# MCU_SCHEM_REV1.net
KiCad netlist of a schematic drawn in Altium Designer
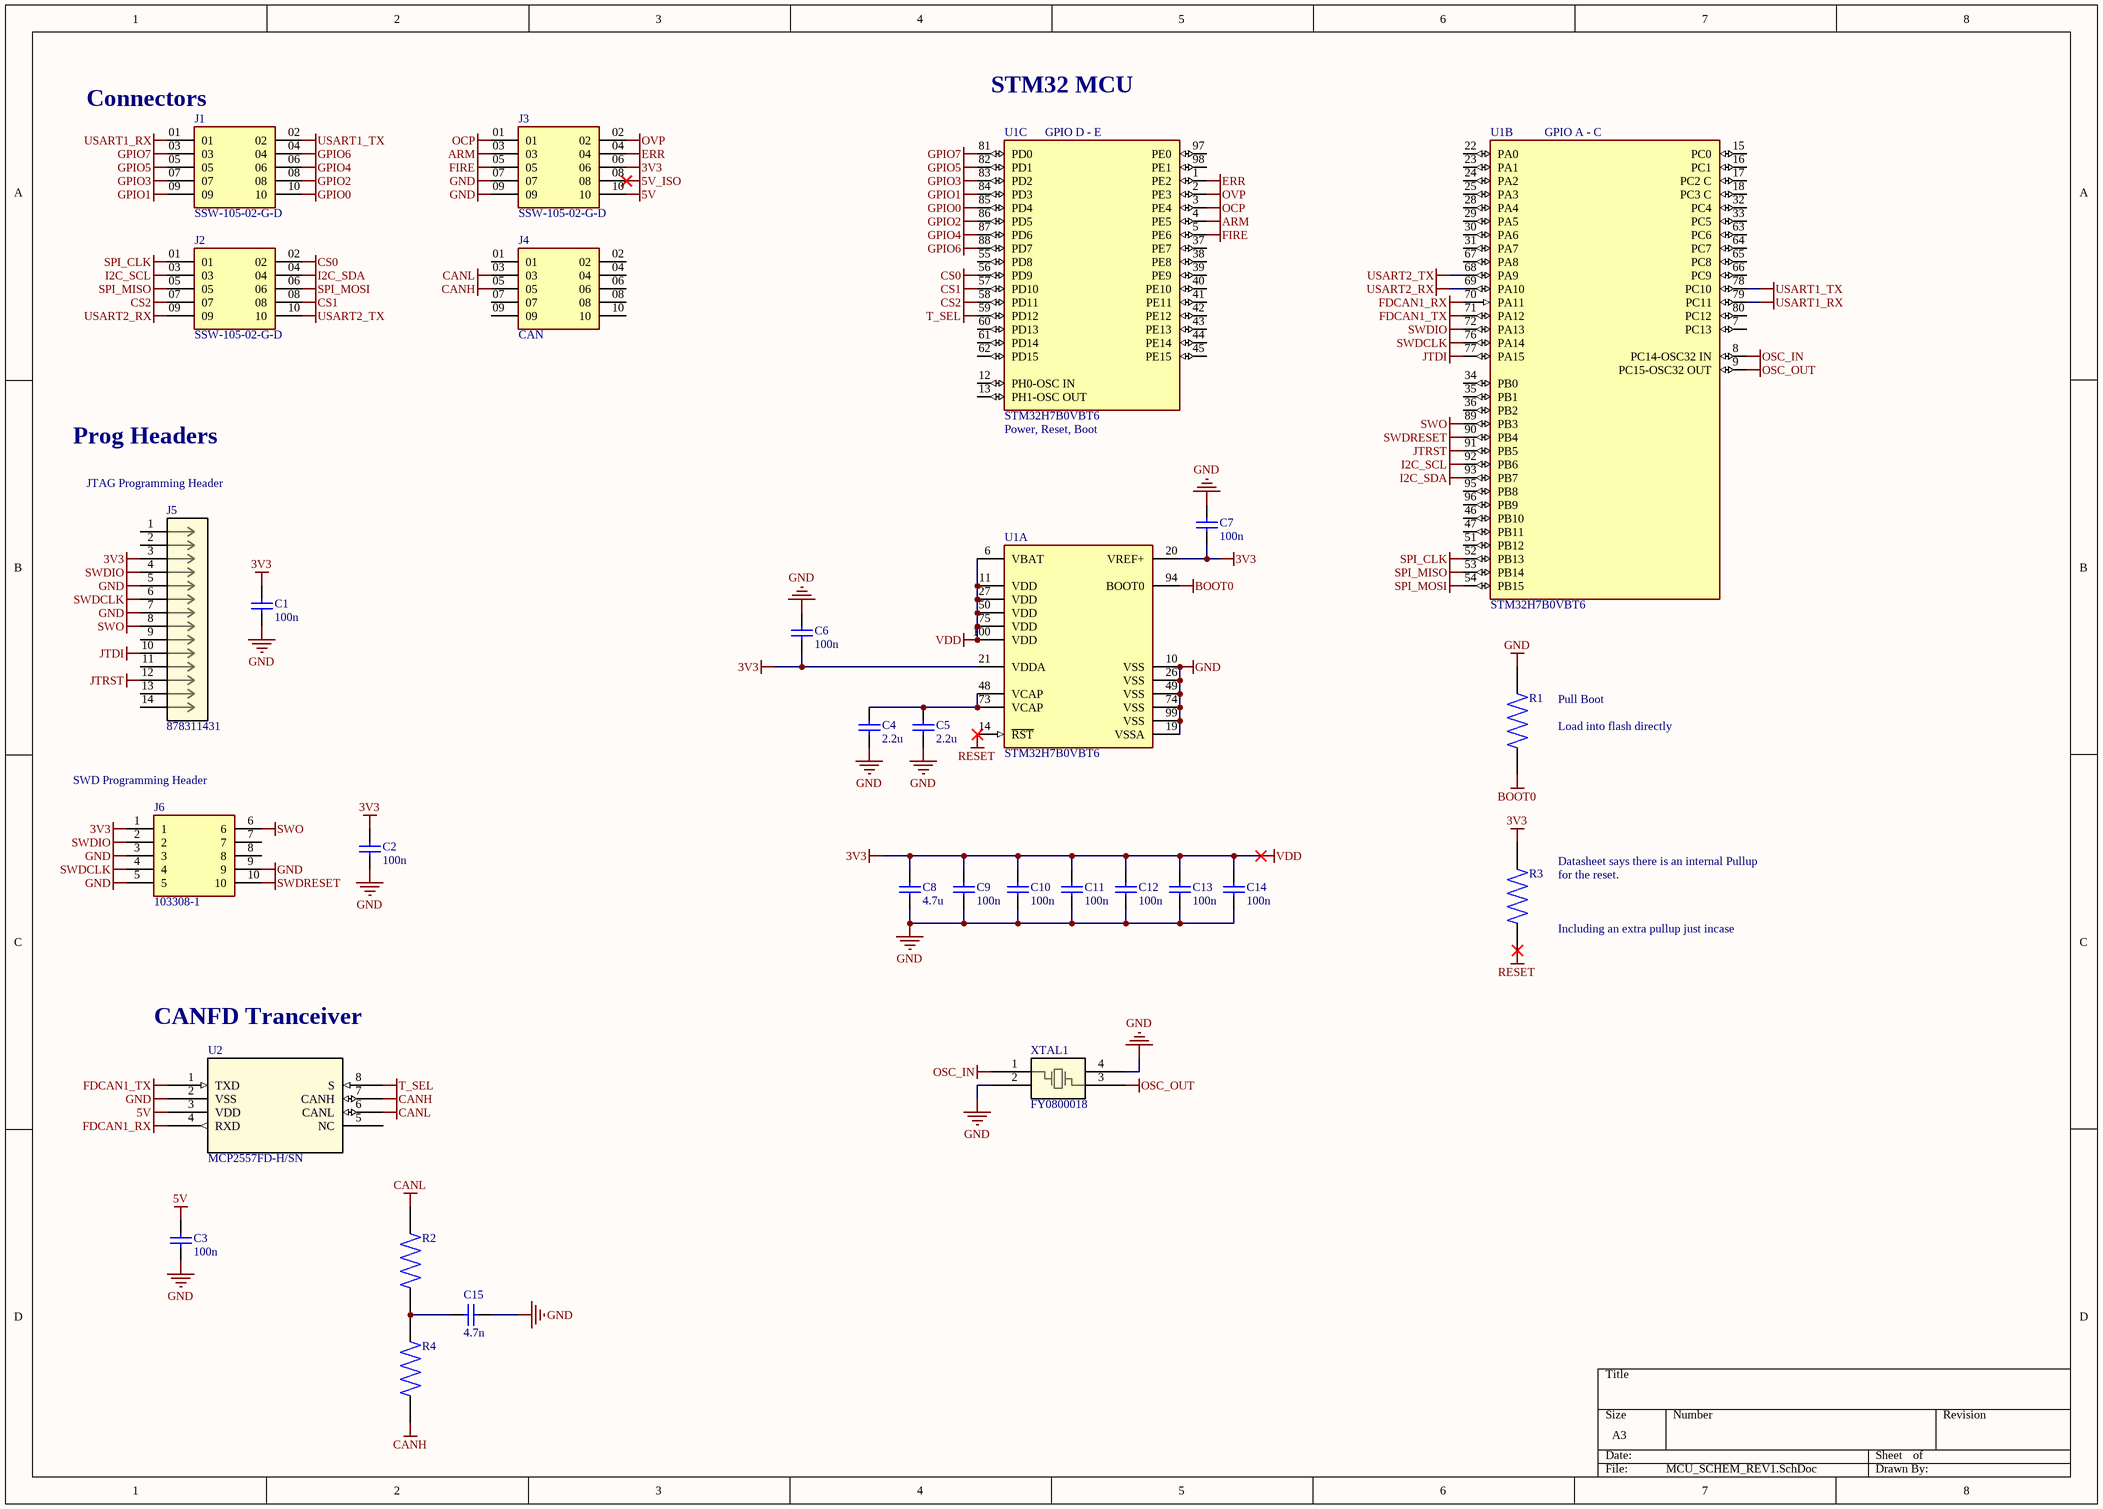
[diagram p0: MCU_SCHEM_REV1.SchDoc]

(export (version "E")
  (design (tool "Eeschema 10.0.6"))
  (components
    (comp (ref "C1")
      (value "100n")
      (footprint "CAPC2013X145X48NL20T23")
      (description "100u")
      (fields (field (name "MANUFACTURER") "Vitramon") (field (name "PART NUMBER") "VJ0805Y682KXAMT"))
      (libsource (lib "0805cap") (part "CMP-2007-03205-1"))
    )
    (comp (ref "C2")
      (value "100n")
      (footprint "CAPC2013X145X48NL20T23")
      (description "100u")
      (fields (field (name "MANUFACTURER") "Vitramon") (field (name "PART NUMBER") "VJ0805Y682KXAMT"))
      (libsource (lib "0805cap") (part "CMP-2007-03205-1"))
    )
    (comp (ref "C3")
      (value "100n")
      (footprint "CAPC2013X145X48NL20T23")
      (description "100u")
      (fields (field (name "MANUFACTURER") "Vitramon") (field (name "PART NUMBER") "VJ0805Y682KXAMT"))
      (libsource (lib "0805cap") (part "CMP-2007-03205-1"))
    )
    (comp (ref "C4")
      (value "2.2u")
      (footprint "CAPC2013X145X48NL20T23")
      (description "100u")
      (fields (field (name "MANUFACTURER") "Vitramon") (field (name "PART NUMBER") "VJ0805Y682KXAMT"))
      (libsource (lib "0805cap") (part "CMP-2007-03205-1"))
    )
    (comp (ref "C5")
      (value "2.2u")
      (footprint "CAPC2013X145X48NL20T23")
      (description "100u")
      (fields (field (name "MANUFACTURER") "Vitramon") (field (name "PART NUMBER") "VJ0805Y682KXAMT"))
      (libsource (lib "0805cap") (part "CMP-2007-03205-1"))
    )
    (comp (ref "C6")
      (value "100n")
      (footprint "CAPC2013X145X48NL20T23")
      (description "100u")
      (fields (field (name "MANUFACTURER") "Vitramon") (field (name "PART NUMBER") "VJ0805Y682KXAMT"))
      (libsource (lib "0805cap") (part "CMP-2007-03205-1"))
    )
    (comp (ref "C7")
      (value "100n")
      (footprint "CAPC2013X145X48NL20T23")
      (description "100u")
      (fields (field (name "MANUFACTURER") "Vitramon") (field (name "PART NUMBER") "VJ0805Y682KXAMT"))
      (libsource (lib "0805cap") (part "CMP-2007-03205-1"))
    )
    (comp (ref "C8")
      (value "4.7u")
      (footprint "CAPC2013X145X48NL20T23")
      (description "100u")
      (fields (field (name "MANUFACTURER") "Vitramon") (field (name "PART NUMBER") "VJ0805Y682KXAMT"))
      (libsource (lib "0805cap") (part "CMP-2007-03205-1"))
    )
    (comp (ref "C9")
      (value "100n")
      (footprint "CAPC2013X145X48NL20T23")
      (description "100u")
      (fields (field (name "MANUFACTURER") "Vitramon") (field (name "PART NUMBER") "VJ0805Y682KXAMT"))
      (libsource (lib "0805cap") (part "CMP-2007-03205-1"))
    )
    (comp (ref "C10")
      (value "100n")
      (footprint "CAPC2013X145X48NL20T23")
      (description "100u")
      (fields (field (name "MANUFACTURER") "Vitramon") (field (name "PART NUMBER") "VJ0805Y682KXAMT"))
      (libsource (lib "0805cap") (part "CMP-2007-03205-1"))
    )
    (comp (ref "C11")
      (value "100n")
      (footprint "CAPC2013X145X48NL20T23")
      (description "100u")
      (fields (field (name "MANUFACTURER") "Vitramon") (field (name "PART NUMBER") "VJ0805Y682KXAMT"))
      (libsource (lib "0805cap") (part "CMP-2007-03205-1"))
    )
    (comp (ref "C12")
      (value "100n")
      (footprint "CAPC2013X145X48NL20T23")
      (description "100u")
      (fields (field (name "MANUFACTURER") "Vitramon") (field (name "PART NUMBER") "VJ0805Y682KXAMT"))
      (libsource (lib "0805cap") (part "CMP-2007-03205-1"))
    )
    (comp (ref "C13")
      (value "100n")
      (footprint "CAPC2013X145X48NL20T23")
      (description "100u")
      (fields (field (name "MANUFACTURER") "Vitramon") (field (name "PART NUMBER") "VJ0805Y682KXAMT"))
      (libsource (lib "0805cap") (part "CMP-2007-03205-1"))
    )
    (comp (ref "C14")
      (value "100n")
      (footprint "CAPC2013X145X48NL20T23")
      (description "100u")
      (fields (field (name "MANUFACTURER") "Vitramon") (field (name "PART NUMBER") "VJ0805Y682KXAMT"))
      (libsource (lib "0805cap") (part "CMP-2007-03205-1"))
    )
    (comp (ref "C15")
      (value "4.7n")
      (footprint "CAPC2013X145X48NL20T23")
      (description "100u")
      (fields (field (name "MANUFACTURER") "Vitramon") (field (name "PART NUMBER") "VJ0805Y682KXAMT"))
      (libsource (lib "0805cap") (part "CMP-2007-03205-1"))
    )
    (comp (ref "J1")
      (value "SSW-105-02-G-D")
      (footprint "SAMTEC_SSW-105-02-G-D")
      (fields (field (name "MF") "Samtec Inc."))
      (libsource (lib "SSW-105-02-G-D") (part "SSW-105-02-G-D"))
    )
    (comp (ref "J2")
      (value "SSW-105-02-G-D")
      (footprint "SAMTEC_SSW-105-02-G-D")
      (fields (field (name "MF") "Samtec Inc."))
      (libsource (lib "SSW-105-02-G-D") (part "SSW-105-02-G-D"))
    )
    (comp (ref "J3")
      (value "SSW-105-02-G-D")
      (footprint "SAMTEC_SSW-105-02-G-D")
      (fields (field (name "MF") "Samtec Inc."))
      (libsource (lib "SSW-105-02-G-D") (part "SSW-105-02-G-D"))
    )
    (comp (ref "J4")
      (value "CAN")
      (footprint "SAMTEC_SSW-105-02-G-D")
      (fields (field (name "MP") "SSW-105-02-G-D") (field (name "MF") "Samtec Inc."))
      (libsource (lib "SSW-105-02-G-D") (part "SSW-105-02-G-D"))
    )
    (comp (ref "J5")
      (value "878311431")
      (footprint "CONN14_878311431_MOL")
      (fields (field (name "COPYRIGHT") "Copyright (C) 2026 Ultra Librarian. All rights reserved."))
      (libsource (lib "878311431") (part "878311431"))
    )
    (comp (ref "J6")
      (value "103308-1")
      (footprint "TE_103308-1")
      (description "Header;  Pin;  Vertical;  Copper Alloy;  Thermoplastic;  10;  0.100 x 0.100 in.;  1 A")
      (fields (field (name "MF") "TE Connectivity"))
      (libsource (lib "103308-1") (part "103308-1"))
    )
    (comp (ref "R1")
      (value "~")
      (footprint "RESC2012X65N")
      (description "RN 0805 1K0 0.1% 10PPM 5KRL")
      (fields (field (name "MP") "RN73C2A1K0BTD"))
      (libsource (lib "RN73C2A1K0BTD") (part "RN73C2A1K0BTD"))
    )
    (comp (ref "R2")
      (value "~")
      (footprint "RESC2012X65N")
      (description "RN 0805 1K0 0.1% 10PPM 5KRL")
      (fields (field (name "MP") "RN73C2A1K0BTD"))
      (libsource (lib "RN73C2A1K0BTD") (part "RN73C2A1K0BTD"))
    )
    (comp (ref "R3")
      (value "~")
      (footprint "RESC2012X65N")
      (description "RN 0805 1K0 0.1% 10PPM 5KRL")
      (fields (field (name "MP") "RN73C2A1K0BTD"))
      (libsource (lib "RN73C2A1K0BTD") (part "RN73C2A1K0BTD"))
    )
    (comp (ref "R4")
      (value "~")
      (footprint "RESC2012X65N")
      (description "RN 0805 1K0 0.1% 10PPM 5KRL")
      (fields (field (name "MP") "RN73C2A1K0BTD"))
      (libsource (lib "RN73C2A1K0BTD") (part "RN73C2A1K0BTD"))
    )
    (comp (ref "U1")
      (value "STM32H7B0VBT6")
      (footprint "FP-LQFP100-MFG")
      (description "IC MCU 32BIT 128KB FLASH 100LQFP")
      (libsource (lib "Components - 24.10.25 - 18.03") (part "CMP-12105-000109-1"))
    )
    (comp (ref "U2")
      (value "MCP2557FD-H/SN")
      (footprint "SOIC8_SN_MCH")
      (description "No Description Available")
      (fields (field (name "COPYRIGHT") "Copyright (C) 2026 Ultra Librarian. All rights reserved."))
      (libsource (lib "MCP2557FD-HSN") (part "MCP2557FD-HSN"))
    )
    (comp (ref "XTAL1")
      (value "FY0800018")
      (footprint "4xtal- 1-3xtal 2-4NC_DIO")
      (description "Description")
      (fields (field (name "COPYRIGHT") "Copyright (C) 2025 Ultra Librarian. All rights reserved."))
      (libsource (lib "FY0800018") (part "FY0800018"))
    )
  )
  (nets
    (net (code "1") (name "3V3") (class "Default")
      (node (ref "C1") (pin "2") (pinfunction "2_2") (pintype "passive"))
      (node (ref "C10") (pin "2") (pinfunction "2_2") (pintype "passive"))
      (node (ref "C11") (pin "2") (pinfunction "2_2") (pintype "passive"))
      (node (ref "C12") (pin "2") (pinfunction "2_2") (pintype "passive"))
      (node (ref "C13") (pin "2") (pinfunction "2_2") (pintype "passive"))
      (node (ref "C14") (pin "2") (pinfunction "2_2") (pintype "passive"))
      (node (ref "C2") (pin "2") (pinfunction "2_2") (pintype "passive"))
      (node (ref "C6") (pin "1") (pinfunction "1_1") (pintype "passive"))
      (node (ref "C7") (pin "1") (pinfunction "1_1") (pintype "passive"))
      (node (ref "C8") (pin "2") (pinfunction "2_2") (pintype "passive"))
      (node (ref "C9") (pin "2") (pinfunction "2_2") (pintype "passive"))
      (node (ref "J3") (pin "06") (pinfunction "06_06") (pintype "passive"))
      (node (ref "J5") (pin "3") (pinfunction "3_3") (pintype "passive"))
      (node (ref "J6") (pin "1") (pinfunction "1_1") (pintype "passive"))
      (node (ref "R3") (pin "2") (pinfunction "2_2") (pintype "passive"))
      (node (ref "U1") (pin "100") (pinfunction "VDD_100") (pintype "power_in"))
      (node (ref "U1") (pin "11") (pinfunction "VDD_11") (pintype "power_in"))
      (node (ref "U1") (pin "20") (pinfunction "VREF+_20") (pintype "passive"))
      (node (ref "U1") (pin "21") (pinfunction "VDDA_21") (pintype "power_in"))
      (node (ref "U1") (pin "27") (pinfunction "VDD_27") (pintype "power_in"))
      (node (ref "U1") (pin "50") (pinfunction "VDD_50") (pintype "power_in"))
      (node (ref "U1") (pin "6") (pinfunction "VBAT_6") (pintype "power_in"))
      (node (ref "U1") (pin "75") (pinfunction "VDD_75") (pintype "power_in"))
    )
    (net (code "2") (name "5V") (class "Default")
      (node (ref "C3") (pin "2") (pinfunction "2_2") (pintype "passive"))
      (node (ref "J3") (pin "10") (pinfunction "10_10") (pintype "passive"))
      (node (ref "U2") (pin "3") (pinfunction "VDD_3") (pintype "power_in"))
    )
    (net (code "3") (name "5V_ISO") (class "Default")
      (node (ref "J3") (pin "08") (pinfunction "08_08") (pintype "passive"))
    )
    (net (code "4") (name "ARM") (class "Default")
      (node (ref "J3") (pin "03") (pinfunction "03_03") (pintype "passive"))
      (node (ref "U1") (pin "4") (pinfunction "PE5_4") (pintype "bidirectional"))
    )
    (net (code "5") (name "BOOT0") (class "Default")
      (node (ref "R1") (pin "1") (pinfunction "1_1") (pintype "passive"))
      (node (ref "U1") (pin "94") (pinfunction "BOOT0_94") (pintype "passive"))
    )
    (net (code "6") (name "CANH") (class "Default")
      (node (ref "J4") (pin "05") (pinfunction "05_05") (pintype "passive"))
      (node (ref "R4") (pin "1") (pinfunction "1_1") (pintype "passive"))
      (node (ref "U2") (pin "7") (pinfunction "CANH_7") (pintype "bidirectional"))
    )
    (net (code "7") (name "CANL") (class "Default")
      (node (ref "J4") (pin "03") (pinfunction "03_03") (pintype "passive"))
      (node (ref "R2") (pin "2") (pinfunction "2_2") (pintype "passive"))
      (node (ref "U2") (pin "6") (pinfunction "CANL_6") (pintype "bidirectional"))
    )
    (net (code "8") (name "CS0") (class "Default")
      (node (ref "J2") (pin "02") (pinfunction "02_02") (pintype "passive"))
      (node (ref "U1") (pin "56") (pinfunction "PD9_56") (pintype "bidirectional"))
    )
    (net (code "9") (name "CS1") (class "Default")
      (node (ref "J2") (pin "08") (pinfunction "08_08") (pintype "passive"))
      (node (ref "U1") (pin "57") (pinfunction "PD10_57") (pintype "bidirectional"))
    )
    (net (code "10") (name "CS2") (class "Default")
      (node (ref "J2") (pin "07") (pinfunction "07_07") (pintype "passive"))
      (node (ref "U1") (pin "58") (pinfunction "PD11_58") (pintype "bidirectional"))
    )
    (net (code "11") (name "ERR") (class "Default")
      (node (ref "J3") (pin "04") (pinfunction "04_04") (pintype "passive"))
      (node (ref "U1") (pin "1") (pinfunction "PE2_1") (pintype "bidirectional"))
    )
    (net (code "12") (name "FDCAN1_RX") (class "Default")
      (node (ref "U1") (pin "70") (pinfunction "PA11_70") (pintype "bidirectional"))
      (node (ref "U2") (pin "4") (pinfunction "RXD_4") (pintype "output"))
    )
    (net (code "13") (name "FDCAN1_TX") (class "Default")
      (node (ref "U1") (pin "71") (pinfunction "PA12_71") (pintype "bidirectional"))
      (node (ref "U2") (pin "1") (pinfunction "TXD_1") (pintype "input"))
    )
    (net (code "14") (name "FIRE") (class "Default")
      (node (ref "J3") (pin "05") (pinfunction "05_05") (pintype "passive"))
      (node (ref "U1") (pin "5") (pinfunction "PE6_5") (pintype "bidirectional"))
    )
    (net (code "15") (name "GND") (class "Default")
      (node (ref "C1") (pin "1") (pinfunction "1_1") (pintype "passive"))
      (node (ref "C10") (pin "1") (pinfunction "1_1") (pintype "passive"))
      (node (ref "C11") (pin "1") (pinfunction "1_1") (pintype "passive"))
      (node (ref "C12") (pin "1") (pinfunction "1_1") (pintype "passive"))
      (node (ref "C13") (pin "1") (pinfunction "1_1") (pintype "passive"))
      (node (ref "C14") (pin "1") (pinfunction "1_1") (pintype "passive"))
      (node (ref "C15") (pin "1") (pinfunction "1_1") (pintype "passive"))
      (node (ref "C2") (pin "1") (pinfunction "1_1") (pintype "passive"))
      (node (ref "C3") (pin "1") (pinfunction "1_1") (pintype "passive"))
      (node (ref "C4") (pin "1") (pinfunction "1_1") (pintype "passive"))
      (node (ref "C5") (pin "1") (pinfunction "1_1") (pintype "passive"))
      (node (ref "C6") (pin "2") (pinfunction "2_2") (pintype "passive"))
      (node (ref "C7") (pin "2") (pinfunction "2_2") (pintype "passive"))
      (node (ref "C8") (pin "1") (pinfunction "1_1") (pintype "passive"))
      (node (ref "C9") (pin "1") (pinfunction "1_1") (pintype "passive"))
      (node (ref "J3") (pin "07") (pinfunction "07_07") (pintype "passive"))
      (node (ref "J3") (pin "09") (pinfunction "09_09") (pintype "passive"))
      (node (ref "J5") (pin "5") (pinfunction "5_5") (pintype "passive"))
      (node (ref "J5") (pin "7") (pinfunction "7_7") (pintype "passive"))
      (node (ref "J6") (pin "3") (pinfunction "3_3") (pintype "passive"))
      (node (ref "J6") (pin "5") (pinfunction "5_5") (pintype "passive"))
      (node (ref "J6") (pin "9") (pinfunction "9_9") (pintype "passive"))
      (node (ref "R1") (pin "2") (pinfunction "2_2") (pintype "passive"))
      (node (ref "U1") (pin "10") (pinfunction "VSS_10") (pintype "power_in"))
      (node (ref "U1") (pin "19") (pinfunction "VSSA_19") (pintype "power_in"))
      (node (ref "U1") (pin "26") (pinfunction "VSS_26") (pintype "power_in"))
      (node (ref "U1") (pin "49") (pinfunction "VSS_49") (pintype "power_in"))
      (node (ref "U1") (pin "74") (pinfunction "VSS_74") (pintype "power_in"))
      (node (ref "U1") (pin "99") (pinfunction "VSS_99") (pintype "power_in"))
      (node (ref "U2") (pin "2") (pinfunction "VSS_2") (pintype "power_in"))
      (node (ref "XTAL1") (pin "2") (pinfunction "2_2") (pintype "passive"))
      (node (ref "XTAL1") (pin "4") (pinfunction "4_4") (pintype "passive"))
    )
    (net (code "16") (name "GPIO0") (class "Default")
      (node (ref "J1") (pin "10") (pinfunction "10_10") (pintype "passive"))
      (node (ref "U1") (pin "85") (pinfunction "PD4_85") (pintype "bidirectional"))
    )
    (net (code "17") (name "GPIO1") (class "Default")
      (node (ref "J1") (pin "09") (pinfunction "09_09") (pintype "passive"))
      (node (ref "U1") (pin "84") (pinfunction "PD3_84") (pintype "bidirectional"))
    )
    (net (code "18") (name "GPIO2") (class "Default")
      (node (ref "J1") (pin "08") (pinfunction "08_08") (pintype "passive"))
      (node (ref "U1") (pin "86") (pinfunction "PD5_86") (pintype "bidirectional"))
    )
    (net (code "19") (name "GPIO3") (class "Default")
      (node (ref "J1") (pin "07") (pinfunction "07_07") (pintype "passive"))
      (node (ref "U1") (pin "83") (pinfunction "PD2_83") (pintype "bidirectional"))
    )
    (net (code "20") (name "GPIO4") (class "Default")
      (node (ref "J1") (pin "06") (pinfunction "06_06") (pintype "passive"))
      (node (ref "U1") (pin "87") (pinfunction "PD6_87") (pintype "bidirectional"))
    )
    (net (code "21") (name "GPIO5") (class "Default")
      (node (ref "J1") (pin "05") (pinfunction "05_05") (pintype "passive"))
      (node (ref "U1") (pin "82") (pinfunction "PD1_82") (pintype "bidirectional"))
    )
    (net (code "22") (name "GPIO6") (class "Default")
      (node (ref "J1") (pin "04") (pinfunction "04_04") (pintype "passive"))
      (node (ref "U1") (pin "88") (pinfunction "PD7_88") (pintype "bidirectional"))
    )
    (net (code "23") (name "GPIO7") (class "Default")
      (node (ref "J1") (pin "03") (pinfunction "03_03") (pintype "passive"))
      (node (ref "U1") (pin "81") (pinfunction "PD0_81") (pintype "bidirectional"))
    )
    (net (code "24") (name "I2C_SCL") (class "Default")
      (node (ref "J2") (pin "03") (pinfunction "03_03") (pintype "passive"))
      (node (ref "U1") (pin "92") (pinfunction "PB6_92") (pintype "bidirectional"))
    )
    (net (code "25") (name "I2C_SDA") (class "Default")
      (node (ref "J2") (pin "04") (pinfunction "04_04") (pintype "passive"))
      (node (ref "U1") (pin "93") (pinfunction "PB7_93") (pintype "bidirectional"))
    )
    (net (code "26") (name "JTDI") (class "Default")
      (node (ref "J5") (pin "10") (pinfunction "10_10") (pintype "passive"))
      (node (ref "U1") (pin "77") (pinfunction "PA15_77") (pintype "bidirectional"))
    )
    (net (code "27") (name "JTRST") (class "Default")
      (node (ref "J5") (pin "12") (pinfunction "12_12") (pintype "passive"))
      (node (ref "U1") (pin "91") (pinfunction "PB5_91") (pintype "bidirectional"))
    )
    (net (code "28") (name "Net-(C4-Pad2)") (class "Default")
      (node (ref "C4") (pin "2") (pinfunction "2_2") (pintype "passive"))
      (node (ref "C5") (pin "2") (pinfunction "2_2") (pintype "passive"))
      (node (ref "U1") (pin "48") (pinfunction "VCAP_48") (pintype "passive"))
      (node (ref "U1") (pin "73") (pinfunction "VCAP_73") (pintype "passive"))
    )
    (net (code "29") (name "Net-(C15-Pad2)") (class "Default")
      (node (ref "C15") (pin "2") (pinfunction "2_2") (pintype "passive"))
      (node (ref "R2") (pin "1") (pinfunction "1_1") (pintype "passive"))
      (node (ref "R4") (pin "2") (pinfunction "2_2") (pintype "passive"))
    )
    (net (code "30") (name "OCP") (class "Default")
      (node (ref "J3") (pin "01") (pinfunction "01_01") (pintype "passive"))
      (node (ref "U1") (pin "3") (pinfunction "PE4_3") (pintype "bidirectional"))
    )
    (net (code "31") (name "OSC_IN") (class "Default")
      (node (ref "U1") (pin "8") (pinfunction "PC14-OSC32_IN_8") (pintype "bidirectional"))
      (node (ref "XTAL1") (pin "1") (pinfunction "1_1") (pintype "passive"))
    )
    (net (code "32") (name "OSC_OUT") (class "Default")
      (node (ref "U1") (pin "9") (pinfunction "PC15-OSC32_OUT_9") (pintype "bidirectional"))
      (node (ref "XTAL1") (pin "3") (pinfunction "3_3") (pintype "passive"))
    )
    (net (code "33") (name "OVP") (class "Default")
      (node (ref "J3") (pin "02") (pinfunction "02_02") (pintype "passive"))
      (node (ref "U1") (pin "2") (pinfunction "PE3_2") (pintype "bidirectional"))
    )
    (net (code "34") (name "RESET") (class "Default")
      (node (ref "R3") (pin "1") (pinfunction "1_1") (pintype "passive"))
      (node (ref "U1") (pin "14") (pinfunction "~{RST}_14") (pintype "input"))
    )
    (net (code "35") (name "SPI_CLK") (class "Default")
      (node (ref "J2") (pin "01") (pinfunction "01_01") (pintype "passive"))
      (node (ref "U1") (pin "52") (pinfunction "PB13_52") (pintype "bidirectional"))
    )
    (net (code "36") (name "SPI_MISO") (class "Default")
      (node (ref "J2") (pin "05") (pinfunction "05_05") (pintype "passive"))
      (node (ref "U1") (pin "53") (pinfunction "PB14_53") (pintype "bidirectional"))
    )
    (net (code "37") (name "SPI_MOSI") (class "Default")
      (node (ref "J2") (pin "06") (pinfunction "06_06") (pintype "passive"))
      (node (ref "U1") (pin "54") (pinfunction "PB15_54") (pintype "bidirectional"))
    )
    (net (code "38") (name "SWDCLK") (class "Default")
      (node (ref "J5") (pin "6") (pinfunction "6_6") (pintype "passive"))
      (node (ref "J6") (pin "4") (pinfunction "4_4") (pintype "passive"))
      (node (ref "U1") (pin "76") (pinfunction "PA14_76") (pintype "bidirectional"))
    )
    (net (code "39") (name "SWDIO") (class "Default")
      (node (ref "J5") (pin "4") (pinfunction "4_4") (pintype "passive"))
      (node (ref "J6") (pin "2") (pinfunction "2_2") (pintype "passive"))
      (node (ref "U1") (pin "72") (pinfunction "PA13_72") (pintype "bidirectional"))
    )
    (net (code "40") (name "SWDRESET") (class "Default")
      (node (ref "J6") (pin "10") (pinfunction "10_10") (pintype "passive"))
      (node (ref "U1") (pin "90") (pinfunction "PB4_90") (pintype "bidirectional"))
    )
    (net (code "41") (name "SWO") (class "Default")
      (node (ref "J5") (pin "8") (pinfunction "8_8") (pintype "passive"))
      (node (ref "J6") (pin "6") (pinfunction "6_6") (pintype "passive"))
      (node (ref "U1") (pin "89") (pinfunction "PB3_89") (pintype "bidirectional"))
    )
    (net (code "42") (name "T_SEL") (class "Default")
      (node (ref "U1") (pin "59") (pinfunction "PD12_59") (pintype "bidirectional"))
      (node (ref "U2") (pin "8") (pinfunction "S_8") (pintype "input"))
    )
    (net (code "43") (name "USART1_RX") (class "Default")
      (node (ref "J1") (pin "01") (pinfunction "01_01") (pintype "passive"))
      (node (ref "U1") (pin "79") (pinfunction "PC11_79") (pintype "bidirectional"))
    )
    (net (code "44") (name "USART1_TX") (class "Default")
      (node (ref "J1") (pin "02") (pinfunction "02_02") (pintype "passive"))
      (node (ref "U1") (pin "78") (pinfunction "PC10_78") (pintype "bidirectional"))
    )
    (net (code "45") (name "USART2_RX") (class "Default")
      (node (ref "J2") (pin "09") (pinfunction "09_09") (pintype "passive"))
      (node (ref "U1") (pin "69") (pinfunction "PA10_69") (pintype "bidirectional"))
    )
    (net (code "46") (name "USART2_TX") (class "Default")
      (node (ref "J2") (pin "10") (pinfunction "10_10") (pintype "passive"))
      (node (ref "U1") (pin "68") (pinfunction "PA9_68") (pintype "bidirectional"))
    )
    (net (code "47") (name "unconnected-(J4-Pad01)") (class "Default")
      (node (ref "J4") (pin "01") (pinfunction "01_01") (pintype "passive"))
    )
    (net (code "48") (name "unconnected-(J4-Pad02)") (class "Default")
      (node (ref "J4") (pin "02") (pinfunction "02_02") (pintype "passive"))
    )
    (net (code "49") (name "unconnected-(J4-Pad04)") (class "Default")
      (node (ref "J4") (pin "04") (pinfunction "04_04") (pintype "passive"))
    )
    (net (code "50") (name "unconnected-(J4-Pad06)") (class "Default")
      (node (ref "J4") (pin "06") (pinfunction "06_06") (pintype "passive"))
    )
    (net (code "51") (name "unconnected-(J4-Pad07)") (class "Default")
      (node (ref "J4") (pin "07") (pinfunction "07_07") (pintype "passive"))
    )
    (net (code "52") (name "unconnected-(J4-Pad08)") (class "Default")
      (node (ref "J4") (pin "08") (pinfunction "08_08") (pintype "passive"))
    )
    (net (code "53") (name "unconnected-(J4-Pad09)") (class "Default")
      (node (ref "J4") (pin "09") (pinfunction "09_09") (pintype "passive"))
    )
    (net (code "54") (name "unconnected-(J4-Pad10)") (class "Default")
      (node (ref "J4") (pin "10") (pinfunction "10_10") (pintype "passive"))
    )
    (net (code "55") (name "unconnected-(J5-Pad1)") (class "Default")
      (node (ref "J5") (pin "1") (pinfunction "1_1") (pintype "passive"))
    )
    (net (code "56") (name "unconnected-(J5-Pad2)") (class "Default")
      (node (ref "J5") (pin "2") (pinfunction "2_2") (pintype "passive"))
    )
    (net (code "57") (name "unconnected-(J5-Pad9)") (class "Default")
      (node (ref "J5") (pin "9") (pinfunction "9_9") (pintype "passive"))
    )
    (net (code "58") (name "unconnected-(J5-Pad11)") (class "Default")
      (node (ref "J5") (pin "11") (pinfunction "11_11") (pintype "passive"))
    )
    (net (code "59") (name "unconnected-(J5-Pad13)") (class "Default")
      (node (ref "J5") (pin "13") (pinfunction "13_13") (pintype "passive"))
    )
    (net (code "60") (name "unconnected-(J5-Pad14)") (class "Default")
      (node (ref "J5") (pin "14") (pinfunction "14_14") (pintype "passive"))
    )
    (net (code "61") (name "unconnected-(J6-Pad7)") (class "Default")
      (node (ref "J6") (pin "7") (pinfunction "7_7") (pintype "passive"))
    )
    (net (code "62") (name "unconnected-(J6-Pad8)") (class "Default")
      (node (ref "J6") (pin "8") (pinfunction "8_8") (pintype "passive"))
    )
    (net (code "63") (name "unconnected-(U1B-PA0-Pad22)") (class "Default")
      (node (ref "U1") (pin "22") (pinfunction "PA0_22") (pintype "bidirectional"))
    )
    (net (code "64") (name "unconnected-(U1B-PA1-Pad23)") (class "Default")
      (node (ref "U1") (pin "23") (pinfunction "PA1_23") (pintype "bidirectional"))
    )
    (net (code "65") (name "unconnected-(U1B-PA2-Pad24)") (class "Default")
      (node (ref "U1") (pin "24") (pinfunction "PA2_24") (pintype "bidirectional"))
    )
    (net (code "66") (name "unconnected-(U1B-PA3-Pad25)") (class "Default")
      (node (ref "U1") (pin "25") (pinfunction "PA3_25") (pintype "bidirectional"))
    )
    (net (code "67") (name "unconnected-(U1B-PA4-Pad28)") (class "Default")
      (node (ref "U1") (pin "28") (pinfunction "PA4_28") (pintype "bidirectional"))
    )
    (net (code "68") (name "unconnected-(U1B-PA5-Pad29)") (class "Default")
      (node (ref "U1") (pin "29") (pinfunction "PA5_29") (pintype "bidirectional"))
    )
    (net (code "69") (name "unconnected-(U1B-PA6-Pad30)") (class "Default")
      (node (ref "U1") (pin "30") (pinfunction "PA6_30") (pintype "bidirectional"))
    )
    (net (code "70") (name "unconnected-(U1B-PA7-Pad31)") (class "Default")
      (node (ref "U1") (pin "31") (pinfunction "PA7_31") (pintype "bidirectional"))
    )
    (net (code "71") (name "unconnected-(U1B-PA8-Pad67)") (class "Default")
      (node (ref "U1") (pin "67") (pinfunction "PA8_67") (pintype "bidirectional"))
    )
    (net (code "72") (name "unconnected-(U1B-PB0-Pad34)") (class "Default")
      (node (ref "U1") (pin "34") (pinfunction "PB0_34") (pintype "bidirectional"))
    )
    (net (code "73") (name "unconnected-(U1B-PB1-Pad35)") (class "Default")
      (node (ref "U1") (pin "35") (pinfunction "PB1_35") (pintype "bidirectional"))
    )
    (net (code "74") (name "unconnected-(U1B-PB2-Pad36)") (class "Default")
      (node (ref "U1") (pin "36") (pinfunction "PB2_36") (pintype "bidirectional"))
    )
    (net (code "75") (name "unconnected-(U1B-PB8-Pad95)") (class "Default")
      (node (ref "U1") (pin "95") (pinfunction "PB8_95") (pintype "bidirectional"))
    )
    (net (code "76") (name "unconnected-(U1B-PB9-Pad96)") (class "Default")
      (node (ref "U1") (pin "96") (pinfunction "PB9_96") (pintype "bidirectional"))
    )
    (net (code "77") (name "unconnected-(U1B-PB10-Pad46)") (class "Default")
      (node (ref "U1") (pin "46") (pinfunction "PB10_46") (pintype "bidirectional"))
    )
    (net (code "78") (name "unconnected-(U1B-PB11-Pad47)") (class "Default")
      (node (ref "U1") (pin "47") (pinfunction "PB11_47") (pintype "bidirectional"))
    )
    (net (code "79") (name "unconnected-(U1B-PB12-Pad51)") (class "Default")
      (node (ref "U1") (pin "51") (pinfunction "PB12_51") (pintype "bidirectional"))
    )
    (net (code "80") (name "unconnected-(U1B-PC0-Pad15)") (class "Default")
      (node (ref "U1") (pin "15") (pinfunction "PC0_15") (pintype "bidirectional"))
    )
    (net (code "81") (name "unconnected-(U1B-PC1-Pad16)") (class "Default")
      (node (ref "U1") (pin "16") (pinfunction "PC1_16") (pintype "bidirectional"))
    )
    (net (code "82") (name "unconnected-(U1B-PC2_C-Pad17)") (class "Default")
      (node (ref "U1") (pin "17") (pinfunction "PC2_C_17") (pintype "bidirectional"))
    )
    (net (code "83") (name "unconnected-(U1B-PC3_C-Pad18)") (class "Default")
      (node (ref "U1") (pin "18") (pinfunction "PC3_C_18") (pintype "bidirectional"))
    )
    (net (code "84") (name "unconnected-(U1B-PC4-Pad32)") (class "Default")
      (node (ref "U1") (pin "32") (pinfunction "PC4_32") (pintype "bidirectional"))
    )
    (net (code "85") (name "unconnected-(U1B-PC5-Pad33)") (class "Default")
      (node (ref "U1") (pin "33") (pinfunction "PC5_33") (pintype "bidirectional"))
    )
    (net (code "86") (name "unconnected-(U1B-PC6-Pad63)") (class "Default")
      (node (ref "U1") (pin "63") (pinfunction "PC6_63") (pintype "bidirectional"))
    )
    (net (code "87") (name "unconnected-(U1B-PC7-Pad64)") (class "Default")
      (node (ref "U1") (pin "64") (pinfunction "PC7_64") (pintype "bidirectional"))
    )
    (net (code "88") (name "unconnected-(U1B-PC8-Pad65)") (class "Default")
      (node (ref "U1") (pin "65") (pinfunction "PC8_65") (pintype "bidirectional"))
    )
    (net (code "89") (name "unconnected-(U1B-PC9-Pad66)") (class "Default")
      (node (ref "U1") (pin "66") (pinfunction "PC9_66") (pintype "bidirectional"))
    )
    (net (code "90") (name "unconnected-(U1B-PC12-Pad80)") (class "Default")
      (node (ref "U1") (pin "80") (pinfunction "PC12_80") (pintype "bidirectional"))
    )
    (net (code "91") (name "unconnected-(U1B-PC13-Pad7)") (class "Default")
      (node (ref "U1") (pin "7") (pinfunction "PC13_7") (pintype "bidirectional"))
    )
    (net (code "92") (name "unconnected-(U1C-PD8-Pad55)") (class "Default")
      (node (ref "U1") (pin "55") (pinfunction "PD8_55") (pintype "bidirectional"))
    )
    (net (code "93") (name "unconnected-(U1C-PD13-Pad60)") (class "Default")
      (node (ref "U1") (pin "60") (pinfunction "PD13_60") (pintype "bidirectional"))
    )
    (net (code "94") (name "unconnected-(U1C-PD14-Pad61)") (class "Default")
      (node (ref "U1") (pin "61") (pinfunction "PD14_61") (pintype "bidirectional"))
    )
    (net (code "95") (name "unconnected-(U1C-PD15-Pad62)") (class "Default")
      (node (ref "U1") (pin "62") (pinfunction "PD15_62") (pintype "bidirectional"))
    )
    (net (code "96") (name "unconnected-(U1C-PE0-Pad97)") (class "Default")
      (node (ref "U1") (pin "97") (pinfunction "PE0_97") (pintype "bidirectional"))
    )
    (net (code "97") (name "unconnected-(U1C-PE1-Pad98)") (class "Default")
      (node (ref "U1") (pin "98") (pinfunction "PE1_98") (pintype "bidirectional"))
    )
    (net (code "98") (name "unconnected-(U1C-PE7-Pad37)") (class "Default")
      (node (ref "U1") (pin "37") (pinfunction "PE7_37") (pintype "bidirectional"))
    )
    (net (code "99") (name "unconnected-(U1C-PE8-Pad38)") (class "Default")
      (node (ref "U1") (pin "38") (pinfunction "PE8_38") (pintype "bidirectional"))
    )
    (net (code "100") (name "unconnected-(U1C-PE9-Pad39)") (class "Default")
      (node (ref "U1") (pin "39") (pinfunction "PE9_39") (pintype "bidirectional"))
    )
    (net (code "101") (name "unconnected-(U1C-PE10-Pad40)") (class "Default")
      (node (ref "U1") (pin "40") (pinfunction "PE10_40") (pintype "bidirectional"))
    )
    (net (code "102") (name "unconnected-(U1C-PE11-Pad41)") (class "Default")
      (node (ref "U1") (pin "41") (pinfunction "PE11_41") (pintype "bidirectional"))
    )
    (net (code "103") (name "unconnected-(U1C-PE12-Pad42)") (class "Default")
      (node (ref "U1") (pin "42") (pinfunction "PE12_42") (pintype "bidirectional"))
    )
    (net (code "104") (name "unconnected-(U1C-PE13-Pad43)") (class "Default")
      (node (ref "U1") (pin "43") (pinfunction "PE13_43") (pintype "bidirectional"))
    )
    (net (code "105") (name "unconnected-(U1C-PE14-Pad44)") (class "Default")
      (node (ref "U1") (pin "44") (pinfunction "PE14_44") (pintype "bidirectional"))
    )
    (net (code "106") (name "unconnected-(U1C-PE15-Pad45)") (class "Default")
      (node (ref "U1") (pin "45") (pinfunction "PE15_45") (pintype "bidirectional"))
    )
    (net (code "107") (name "unconnected-(U1C-PH0-OSC_IN-Pad12)") (class "Default")
      (node (ref "U1") (pin "12") (pinfunction "PH0-OSC_IN_12") (pintype "bidirectional"))
    )
    (net (code "108") (name "unconnected-(U1C-PH1-OSC_OUT-Pad13)") (class "Default")
      (node (ref "U1") (pin "13") (pinfunction "PH1-OSC_OUT_13") (pintype "bidirectional"))
    )
    (net (code "109") (name "unconnected-(U2-NC-Pad5)") (class "Default")
      (node (ref "U2") (pin "5") (pinfunction "NC_5") (pintype "passive"))
    )
  )
)
